# NanoRS485-MySens-v008.net
KiCad netlist of a schematic drawn in EAGLE
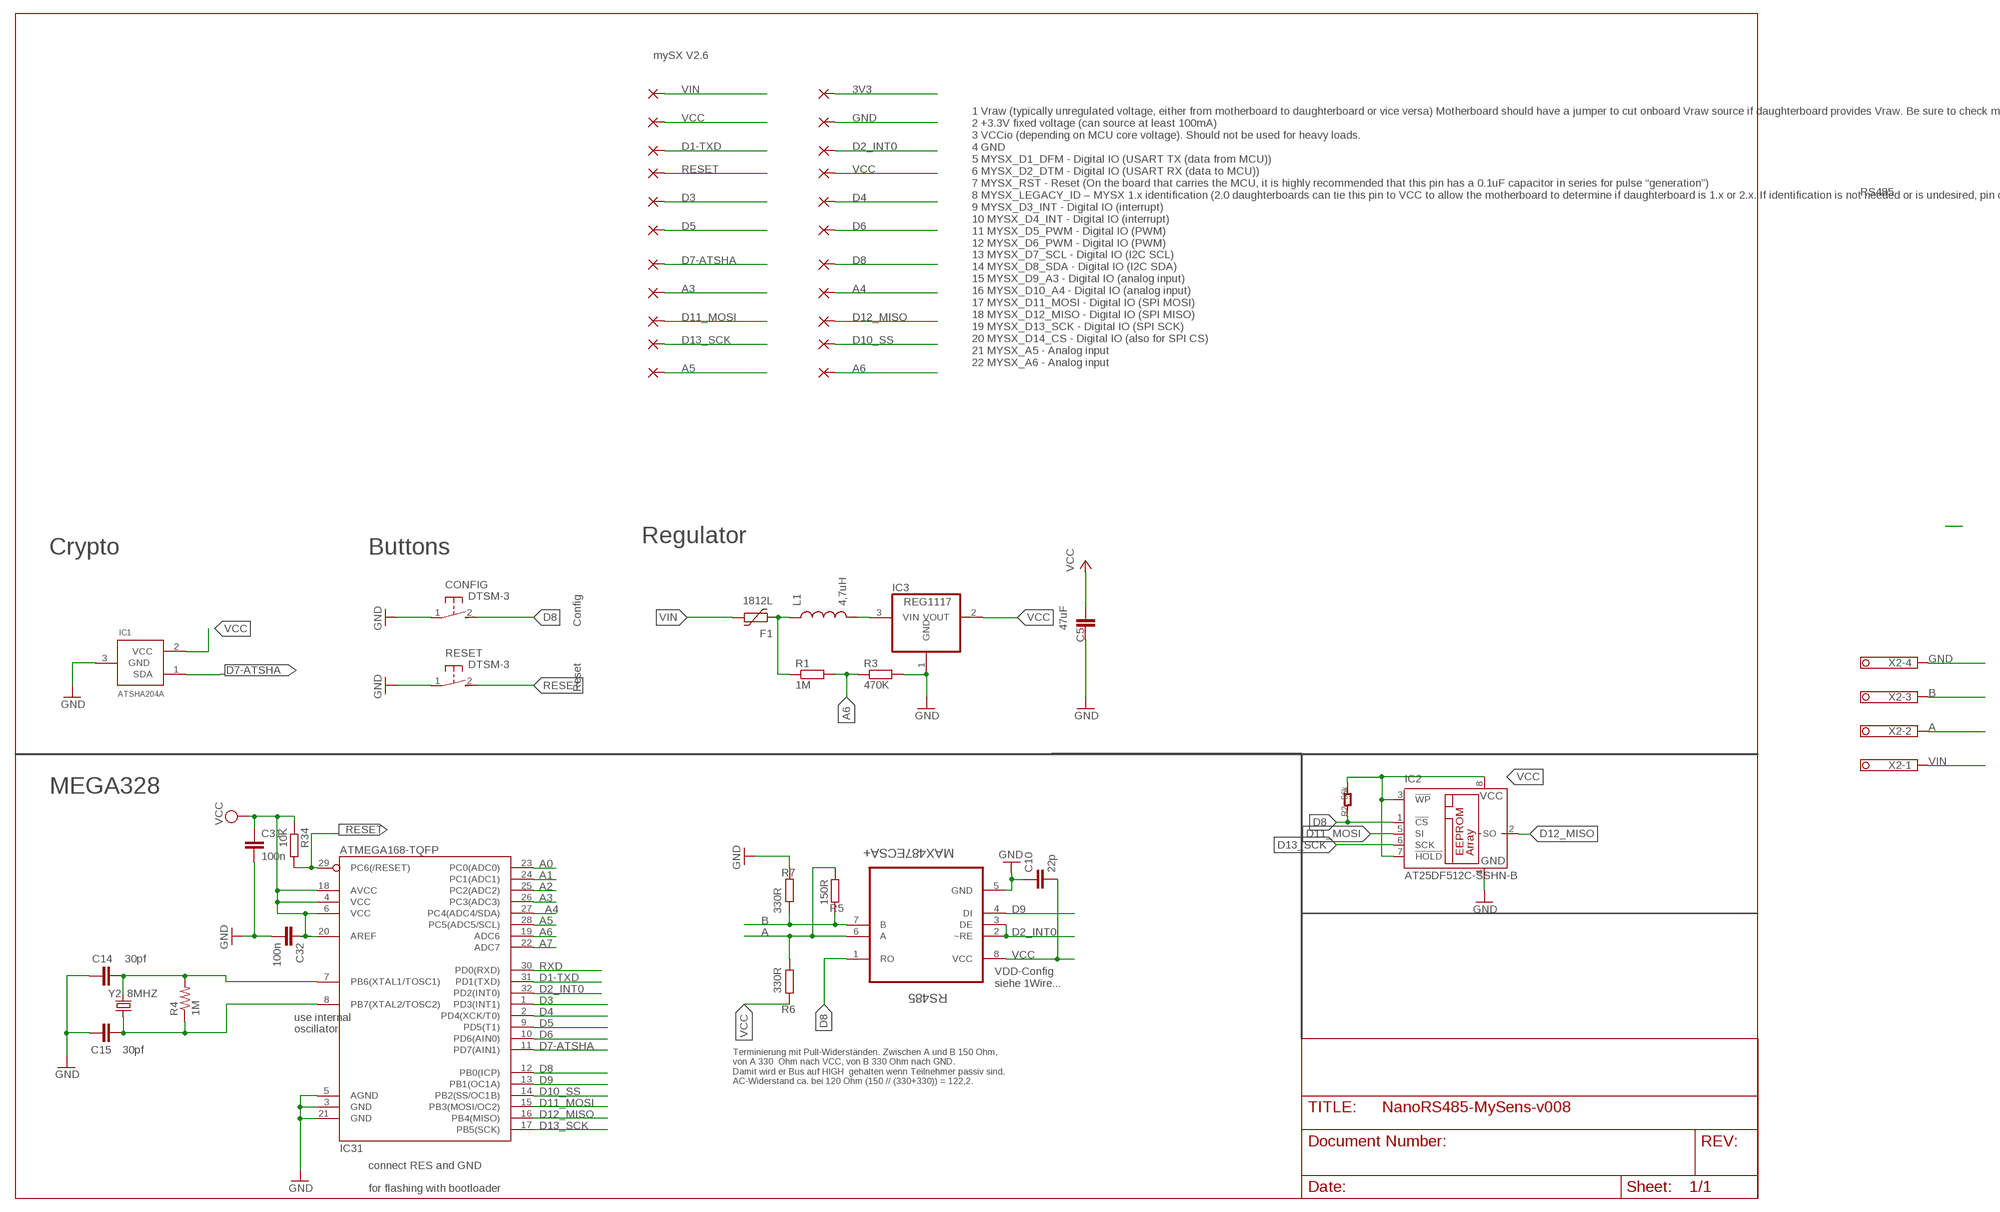
[diagram p0: schematic, sheet 1]

(export (version "E")
  (design (tool "Eeschema 10.0.6"))
  (components
    (comp (ref "3V3")
      (value "WIREPADSMD1,27-254")
      (footprint "eagle-import:SMD1,27-2,54")
      (libsource (lib "eagle-import") (part "WIREPADSMD1,27-254"))
    )
    (comp (ref "A3")
      (value "WIREPADSMD1,27-254")
      (footprint "eagle-import:SMD1,27-2,54")
      (libsource (lib "eagle-import") (part "WIREPADSMD1,27-254"))
    )
    (comp (ref "A4")
      (value "WIREPADSMD1,27-254")
      (footprint "eagle-import:SMD1,27-2,54")
      (libsource (lib "eagle-import") (part "WIREPADSMD1,27-254"))
    )
    (comp (ref "A5")
      (value "WIREPADSMD1,27-254")
      (footprint "eagle-import:SMD1,27-2,54")
      (libsource (lib "eagle-import") (part "WIREPADSMD1,27-254"))
    )
    (comp (ref "A6")
      (value "WIREPADSMD1,27-254")
      (footprint "eagle-import:SMD1,27-2,54")
      (libsource (lib "eagle-import") (part "WIREPADSMD1,27-254"))
    )
    (comp (ref "C5")
      (value "47uF")
      (footprint "eagle-import:C1210")
      (libsource (lib "eagle-import") (part "C-EUC1210"))
    )
    (comp (ref "C10")
      (value "22p")
      (footprint "eagle-import:C0805")
      (libsource (lib "eagle-import") (part "C-EUC0805"))
    )
    (comp (ref "C14")
      (value "30pf")
      (footprint "eagle-import:0805")
      (libsource (lib "eagle-import") (part "CAP0805"))
    )
    (comp (ref "C15")
      (value "30pf")
      (footprint "eagle-import:0805")
      (libsource (lib "eagle-import") (part "CAP0805"))
    )
    (comp (ref "C31")
      (value "100n")
      (footprint "eagle-import:C0805")
      (libsource (lib "eagle-import") (part "C-EUC0805"))
    )
    (comp (ref "C32")
      (value "100n")
      (footprint "eagle-import:C0805")
      (libsource (lib "eagle-import") (part "C-EUC0805"))
    )
    (comp (ref "CONFIG")
      (value "DTSM-3")
      (footprint "eagle-import:DTSM-3")
      (libsource (lib "eagle-import") (part "DTSM-3"))
    )
    (comp (ref "D1")
      (value "WIREPADSMD1,27-254")
      (footprint "eagle-import:SMD1,27-2,54")
      (libsource (lib "eagle-import") (part "WIREPADSMD1,27-254"))
    )
    (comp (ref "D2")
      (value "WIREPADSMD1,27-254")
      (footprint "eagle-import:SMD1,27-2,54")
      (libsource (lib "eagle-import") (part "WIREPADSMD1,27-254"))
    )
    (comp (ref "D3")
      (value "WIREPADSMD1,27-254")
      (footprint "eagle-import:SMD1,27-2,54")
      (libsource (lib "eagle-import") (part "WIREPADSMD1,27-254"))
    )
    (comp (ref "D4")
      (value "WIREPADSMD1,27-254")
      (footprint "eagle-import:SMD1,27-2,54")
      (libsource (lib "eagle-import") (part "WIREPADSMD1,27-254"))
    )
    (comp (ref "D5")
      (value "WIREPADSMD1,27-254")
      (footprint "eagle-import:SMD1,27-2,54")
      (libsource (lib "eagle-import") (part "WIREPADSMD1,27-254"))
    )
    (comp (ref "D6")
      (value "WIREPADSMD1,27-254")
      (footprint "eagle-import:SMD1,27-2,54")
      (libsource (lib "eagle-import") (part "WIREPADSMD1,27-254"))
    )
    (comp (ref "D7")
      (value "WIREPADSMD1,27-254")
      (footprint "eagle-import:SMD1,27-2,54")
      (libsource (lib "eagle-import") (part "WIREPADSMD1,27-254"))
    )
    (comp (ref "D8")
      (value "WIREPADSMD1,27-254")
      (footprint "eagle-import:SMD1,27-2,54")
      (libsource (lib "eagle-import") (part "WIREPADSMD1,27-254"))
    )
    (comp (ref "D10-SS")
      (value "WIREPADSMD1,27-254")
      (footprint "eagle-import:SMD1,27-2,54")
      (libsource (lib "eagle-import") (part "WIREPADSMD1,27-254"))
    )
    (comp (ref "D11")
      (value "WIREPADSMD1,27-254")
      (footprint "eagle-import:SMD1,27-2,54")
      (libsource (lib "eagle-import") (part "WIREPADSMD1,27-254"))
    )
    (comp (ref "D12")
      (value "WIREPADSMD1,27-254")
      (footprint "eagle-import:SMD1,27-2,54")
      (libsource (lib "eagle-import") (part "WIREPADSMD1,27-254"))
    )
    (comp (ref "D13-SCK")
      (value "WIREPADSMD1,27-254")
      (footprint "eagle-import:SMD1,27-2,54")
      (libsource (lib "eagle-import") (part "WIREPADSMD1,27-254"))
    )
    (comp (ref "F1")
      (value "1812L")
      (footprint "eagle-import:1812L")
      (libsource (lib "eagle-import") (part "1812L"))
    )
    (comp (ref "GND")
      (value "WIREPADSMD1,27-254")
      (footprint "eagle-import:SMD1,27-2,54")
      (libsource (lib "eagle-import") (part "WIREPADSMD1,27-254"))
    )
    (comp (ref "IC1")
      (value "ATSHA204A")
      (footprint "eagle-import:SOT23")
      (libsource (lib "eagle-import") (part "ATSHA204A"))
    )
    (comp (ref "IC2")
      (value "AT25DF512C-SSHN-B")
      (footprint "eagle-import:SO-08")
      (fields (field (name "MF") "MICROCHIP") (field (name "MPN") "25AA080/SN"))
      (libsource (lib "eagle-import") (part "25SNAA080"))
    )
    (comp (ref "IC3")
      (value "REG1117")
      (footprint "eagle-import:SOT223")
      (libsource (lib "eagle-import") (part "REG1117"))
    )
    (comp (ref "IC31")
      (value "ATMEGA168-TQFP")
      (footprint "eagle-import:TQFP32-08")
      (libsource (lib "eagle-import") (part "ATMEGA168-TQFP"))
    )
    (comp (ref "L1")
      (value "4,7uH")
      (footprint "eagle-import:0805")
      (libsource (lib "eagle-import") (part "INDUCTOR0805"))
    )
    (comp (ref "R1")
      (value "1M")
      (footprint "eagle-import:R0805")
      (libsource (lib "eagle-import") (part "R-EU_R0805"))
    )
    (comp (ref "R2")
      (value "56k")
      (footprint "eagle-import:R0402")
      (libsource (lib "eagle-import") (part "R-0402"))
    )
    (comp (ref "R3")
      (value "470K")
      (footprint "eagle-import:R0805")
      (libsource (lib "eagle-import") (part "R-EU_R0805"))
    )
    (comp (ref "R4")
      (value "1M")
      (footprint "eagle-import:0805")
      (libsource (lib "eagle-import") (part "RESISTOR0805-RES"))
    )
    (comp (ref "R5")
      (value "150R")
      (footprint "eagle-import:R0805")
      (libsource (lib "eagle-import") (part "R-EU_R0805"))
    )
    (comp (ref "R6")
      (value "330R")
      (footprint "eagle-import:R0805")
      (libsource (lib "eagle-import") (part "R-EU_R0805"))
    )
    (comp (ref "R7")
      (value "330R")
      (footprint "eagle-import:R0805")
      (libsource (lib "eagle-import") (part "R-EU_R0805"))
    )
    (comp (ref "R34")
      (value "10K")
      (footprint "eagle-import:R0805")
      (libsource (lib "eagle-import") (part "R-EU_R0805"))
    )
    (comp (ref "RES")
      (value "WIREPADSMD1,27-254")
      (footprint "eagle-import:SMD1,27-2,54")
      (libsource (lib "eagle-import") (part "WIREPADSMD1,27-254"))
    )
    (comp (ref "RESET")
      (value "DTSM-3")
      (footprint "eagle-import:DTSM-3")
      (libsource (lib "eagle-import") (part "DTSM-3"))
    )
    (comp (ref "RS485")
      (value "MAX487ECSA+")
      (footprint "eagle-import:SOIC127P600X175-8N")
      (libsource (lib "eagle-import") (part "MAX487ECSA+"))
    )
    (comp (ref "VCC")
      (value "WIREPADSMD1,27-254")
      (footprint "eagle-import:SMD1,27-2,54")
      (libsource (lib "eagle-import") (part "WIREPADSMD1,27-254"))
    )
    (comp (ref "VCC-LEGACY")
      (value "WIREPADSMD1,27-254")
      (footprint "eagle-import:SMD1,27-2,54")
      (libsource (lib "eagle-import") (part "WIREPADSMD1,27-254"))
    )
    (comp (ref "VIN")
      (value "WIREPADSMD1,27-254")
      (footprint "eagle-import:SMD1,27-2,54")
      (libsource (lib "eagle-import") (part "WIREPADSMD1,27-254"))
    )
    (comp (ref "X2")
      (value "1751264")
      (footprint "eagle-import:1751264")
      (libsource (lib "eagle-import") (part "1751264"))
    )
    (comp (ref "Y2")
      (value "8MHZ")
      (footprint "eagle-import:CRYSTAL-TXC-7A")
      (libsource (lib "eagle-import") (part "CRYSTALTXC-7A"))
    )
  )
  (nets
    (net (code "1") (name "/3V3") (class "Default")
      (node (ref "3V3") (pin "1") (pinfunction "P_1") (pintype "passive"))
    )
    (net (code "2") (name "/A") (class "Default")
      (node (ref "R5") (pin "1") (pinfunction "1_1") (pintype "passive"))
      (node (ref "R6") (pin "2") (pinfunction "2_2") (pintype "passive"))
      (node (ref "RS485") (pin "6") (pinfunction "A_6") (pintype "bidirectional"))
      (node (ref "X2") (pin "2") (pinfunction "K_2") (pintype "passive"))
    )
    (net (code "3") (name "/A0") (class "Default")
      (node (ref "IC31") (pin "23") (pinfunction "PC0(ADC0)_23") (pintype "bidirectional"))
    )
    (net (code "4") (name "/A1") (class "Default")
      (node (ref "IC31") (pin "24") (pinfunction "PC1(ADC1)_24") (pintype "bidirectional"))
    )
    (net (code "5") (name "/A2") (class "Default")
      (node (ref "IC31") (pin "25") (pinfunction "PC2(ADC2)_25") (pintype "bidirectional"))
    )
    (net (code "6") (name "/A3") (class "Default")
      (node (ref "A3") (pin "1") (pinfunction "P_1") (pintype "passive"))
      (node (ref "IC31") (pin "26") (pinfunction "PC3(ADC3)_26") (pintype "bidirectional"))
    )
    (net (code "7") (name "/A4") (class "Default")
      (node (ref "A4") (pin "1") (pinfunction "P_1") (pintype "passive"))
      (node (ref "IC31") (pin "27") (pinfunction "PC4(ADC4/SDA)_27") (pintype "bidirectional"))
    )
    (net (code "8") (name "/A5") (class "Default")
      (node (ref "A5") (pin "1") (pinfunction "P_1") (pintype "passive"))
      (node (ref "IC31") (pin "28") (pinfunction "PC5(ADC5/SCL)_28") (pintype "bidirectional"))
    )
    (net (code "9") (name "/A7") (class "Default")
      (node (ref "IC31") (pin "22") (pinfunction "ADC7_22") (pintype "bidirectional"))
    )
    (net (code "10") (name "/B") (class "Default")
      (node (ref "R5") (pin "2") (pinfunction "2_2") (pintype "passive"))
      (node (ref "R7") (pin "1") (pinfunction "1_1") (pintype "passive"))
      (node (ref "RS485") (pin "7") (pinfunction "B_7") (pintype "bidirectional"))
      (node (ref "X2") (pin "3") (pinfunction "K_3") (pintype "passive"))
    )
    (net (code "11") (name "/D1-TXD") (class "Default")
      (node (ref "D1") (pin "1") (pinfunction "P_1") (pintype "passive"))
      (node (ref "IC31") (pin "31") (pinfunction "PD1(TXD)_31") (pintype "bidirectional"))
    )
    (net (code "12") (name "/D2_INT0") (class "Default")
      (node (ref "D2") (pin "1") (pinfunction "P_1") (pintype "passive"))
      (node (ref "IC31") (pin "32") (pinfunction "PD2(INT0)_32") (pintype "bidirectional"))
      (node (ref "RS485") (pin "2") (pinfunction "~{RE}_2") (pintype "input"))
      (node (ref "RS485") (pin "3") (pinfunction "DE_3") (pintype "input"))
    )
    (net (code "13") (name "/D3") (class "Default")
      (node (ref "D3") (pin "1") (pinfunction "P_1") (pintype "passive"))
      (node (ref "IC31") (pin "1") (pinfunction "PD3(INT1)_1") (pintype "bidirectional"))
    )
    (net (code "14") (name "/D4") (class "Default")
      (node (ref "D4") (pin "1") (pinfunction "P_1") (pintype "passive"))
      (node (ref "IC31") (pin "2") (pinfunction "PD4(XCK/T0)_2") (pintype "bidirectional"))
    )
    (net (code "15") (name "/D5") (class "Default")
      (node (ref "D5") (pin "1") (pinfunction "P_1") (pintype "passive"))
      (node (ref "IC31") (pin "9") (pinfunction "PD5(T1)_9") (pintype "bidirectional"))
    )
    (net (code "16") (name "/D6") (class "Default")
      (node (ref "D6") (pin "1") (pinfunction "P_1") (pintype "passive"))
      (node (ref "IC31") (pin "10") (pinfunction "PD6(AIN0)_10") (pintype "bidirectional"))
    )
    (net (code "17") (name "/D7-ATSHA") (class "Default")
      (node (ref "D7") (pin "1") (pinfunction "P_1") (pintype "passive"))
      (node (ref "IC1") (pin "1") (pinfunction "SDA_1") (pintype "bidirectional"))
      (node (ref "IC31") (pin "11") (pinfunction "PD7(AIN1)_11") (pintype "bidirectional"))
    )
    (net (code "18") (name "/D9") (class "Default")
      (node (ref "IC31") (pin "13") (pinfunction "PB1(OC1A)_13") (pintype "bidirectional"))
      (node (ref "RS485") (pin "4") (pinfunction "DI_4") (pintype "input"))
    )
    (net (code "19") (name "/D10_SS") (class "Default")
      (node (ref "D10-SS") (pin "1") (pinfunction "P_1") (pintype "passive"))
      (node (ref "IC31") (pin "14") (pinfunction "PB2(SS/OC1B)_14") (pintype "bidirectional"))
    )
    (net (code "20") (name "/RXD") (class "Default")
      (node (ref "IC31") (pin "30") (pinfunction "PD0(RXD)_30") (pintype "bidirectional"))
    )
    (net (code "21") (name "A6") (class "Default")
      (node (ref "A6") (pin "1") (pinfunction "P_1") (pintype "passive"))
      (node (ref "IC31") (pin "19") (pinfunction "ADC6_19") (pintype "bidirectional"))
      (node (ref "R1") (pin "2") (pinfunction "2_2") (pintype "passive"))
      (node (ref "R3") (pin "1") (pinfunction "1_1") (pintype "passive"))
    )
    (net (code "22") (name "D8") (class "Default")
      (node (ref "CONFIG") (pin "2") (pinfunction "2_2") (pintype "passive"))
      (node (ref "D8") (pin "1") (pinfunction "P_1") (pintype "passive"))
      (node (ref "IC2") (pin "1") (pinfunction "~{CS}_1") (pintype "input"))
      (node (ref "IC31") (pin "12") (pinfunction "PB0(ICP)_12") (pintype "bidirectional"))
      (node (ref "R2") (pin "1") (pinfunction "1_1") (pintype "bidirectional"))
      (node (ref "RS485") (pin "1") (pinfunction "RO_1") (pintype "output"))
    )
    (net (code "23") (name "D11_MOSI") (class "Default")
      (node (ref "D11") (pin "1") (pinfunction "P_1") (pintype "passive"))
      (node (ref "IC2") (pin "5") (pinfunction "SI_5") (pintype "input"))
      (node (ref "IC31") (pin "15") (pinfunction "PB3(MOSI/OC2)_15") (pintype "bidirectional"))
    )
    (net (code "24") (name "D12_MISO") (class "Default")
      (node (ref "D12") (pin "1") (pinfunction "P_1") (pintype "passive"))
      (node (ref "IC2") (pin "2") (pinfunction "SO_2") (pintype "bidirectional"))
      (node (ref "IC31") (pin "16") (pinfunction "PB4(MISO)_16") (pintype "bidirectional"))
    )
    (net (code "25") (name "D13_SCK") (class "Default")
      (node (ref "D13-SCK") (pin "1") (pinfunction "P_1") (pintype "passive"))
      (node (ref "IC2") (pin "6") (pinfunction "SCK_6") (pintype "input"))
      (node (ref "IC31") (pin "17") (pinfunction "PB5(SCK)_17") (pintype "bidirectional"))
    )
    (net (code "26") (name "GND") (class "Default")
      (node (ref "C10") (pin "1") (pinfunction "1_1") (pintype "passive"))
      (node (ref "C14") (pin "1") (pinfunction "1_1") (pintype "passive"))
      (node (ref "C15") (pin "1") (pinfunction "1_1") (pintype "passive"))
      (node (ref "C31") (pin "2") (pinfunction "2_2") (pintype "passive"))
      (node (ref "C32") (pin "2") (pinfunction "2_2") (pintype "passive"))
      (node (ref "C5") (pin "1") (pinfunction "1_1") (pintype "passive"))
      (node (ref "CONFIG") (pin "1") (pinfunction "1_1") (pintype "passive"))
      (node (ref "GND") (pin "1") (pinfunction "P_1") (pintype "passive"))
      (node (ref "IC1") (pin "3") (pinfunction "GND_3") (pintype "bidirectional"))
      (node (ref "IC2") (pin "4") (pinfunction "GND_4") (pintype "power_in"))
      (node (ref "IC3") (pin "1") (pinfunction "GND_1") (pintype "power_in"))
      (node (ref "IC31") (pin "21") (pinfunction "GND_21") (pintype "bidirectional"))
      (node (ref "IC31") (pin "3") (pinfunction "GND_3") (pintype "bidirectional"))
      (node (ref "IC31") (pin "5") (pinfunction "AGND_5") (pintype "bidirectional"))
      (node (ref "R3") (pin "2") (pinfunction "2_2") (pintype "passive"))
      (node (ref "R7") (pin "2") (pinfunction "2_2") (pintype "passive"))
      (node (ref "RESET") (pin "1") (pinfunction "1_1") (pintype "passive"))
      (node (ref "RS485") (pin "5") (pinfunction "GND_5") (pintype "passive"))
      (node (ref "X2") (pin "4") (pinfunction "K_4") (pintype "passive"))
    )
    (net (code "27") (name "Net-(F1-1)") (class "Default")
      (node (ref "F1") (pin "P$1") (pinfunction "1_P$1") (pintype "passive"))
      (node (ref "L1") (pin "1") (pinfunction "1_1") (pintype "passive"))
      (node (ref "R1") (pin "1") (pinfunction "1_1") (pintype "passive"))
    )
    (net (code "28") (name "Net-(IC3-VIN)") (class "Default")
      (node (ref "IC3") (pin "3") (pinfunction "VIN_3") (pintype "input"))
      (node (ref "L1") (pin "2") (pinfunction "2_2") (pintype "passive"))
    )
    (net (code "29") (name "Net-(IC31-PB6(XTAL1{slash}TOSC1))") (class "Default")
      (node (ref "C14") (pin "2") (pinfunction "2_2") (pintype "passive"))
      (node (ref "IC31") (pin "7") (pinfunction "PB6(XTAL1/TOSC1)_7") (pintype "bidirectional"))
      (node (ref "R4") (pin "2") (pinfunction "2_2") (pintype "passive"))
      (node (ref "Y2") (pin "P$2") (pinfunction "2_P$2") (pintype "passive"))
    )
    (net (code "30") (name "Net-(IC31-PB7(XTAL2{slash}TOSC2))") (class "Default")
      (node (ref "C15") (pin "2") (pinfunction "2_2") (pintype "passive"))
      (node (ref "IC31") (pin "8") (pinfunction "PB7(XTAL2/TOSC2)_8") (pintype "bidirectional"))
      (node (ref "R4") (pin "1") (pinfunction "1_1") (pintype "passive"))
      (node (ref "Y2") (pin "P$1") (pinfunction "1_P$1") (pintype "passive"))
    )
    (net (code "31") (name "RESET") (class "Default")
      (node (ref "IC31") (pin "29") (pinfunction "PC6(/RESET)_29") (pintype "bidirectional"))
      (node (ref "R34") (pin "2") (pinfunction "2_2") (pintype "passive"))
      (node (ref "RES") (pin "1") (pinfunction "P_1") (pintype "passive"))
      (node (ref "RESET") (pin "2") (pinfunction "2_2") (pintype "passive"))
    )
    (net (code "32") (name "VCC") (class "Default")
      (node (ref "C10") (pin "2") (pinfunction "2_2") (pintype "passive"))
      (node (ref "C31") (pin "1") (pinfunction "1_1") (pintype "passive"))
      (node (ref "C32") (pin "1") (pinfunction "1_1") (pintype "passive"))
      (node (ref "C5") (pin "2") (pinfunction "2_2") (pintype "passive"))
      (node (ref "IC1") (pin "2") (pinfunction "VCC_2") (pintype "bidirectional"))
      (node (ref "IC2") (pin "3") (pinfunction "~{WP}_3") (pintype "input"))
      (node (ref "IC2") (pin "7") (pinfunction "~{HOLD}_7") (pintype "input"))
      (node (ref "IC2") (pin "8") (pinfunction "VCC_8") (pintype "power_in"))
      (node (ref "IC3") (pin "2") (pinfunction "VOUT_2") (pintype "output"))
      (node (ref "IC31") (pin "18") (pinfunction "AVCC_18") (pintype "bidirectional"))
      (node (ref "IC31") (pin "20") (pinfunction "AREF_20") (pintype "bidirectional"))
      (node (ref "IC31") (pin "4") (pinfunction "VCC_4") (pintype "bidirectional"))
      (node (ref "IC31") (pin "6") (pinfunction "VCC_6") (pintype "bidirectional"))
      (node (ref "R2") (pin "2") (pinfunction "2_2") (pintype "bidirectional"))
      (node (ref "R34") (pin "1") (pinfunction "1_1") (pintype "passive"))
      (node (ref "R6") (pin "1") (pinfunction "1_1") (pintype "passive"))
      (node (ref "RS485") (pin "8") (pinfunction "VCC_8") (pintype "power_in"))
      (node (ref "VCC") (pin "1") (pinfunction "P_1") (pintype "passive"))
      (node (ref "VCC-LEGACY") (pin "1") (pinfunction "P_1") (pintype "passive"))
    )
    (net (code "33") (name "VIN") (class "Default")
      (node (ref "F1") (pin "P$2") (pinfunction "2_P$2") (pintype "passive"))
      (node (ref "VIN") (pin "1") (pinfunction "P_1") (pintype "passive"))
      (node (ref "X2") (pin "1") (pinfunction "K_1") (pintype "passive"))
    )
  )
)
